# zb_pt4115_v1_1.net
KiCad netlist of a schematic drawn in EAGLE
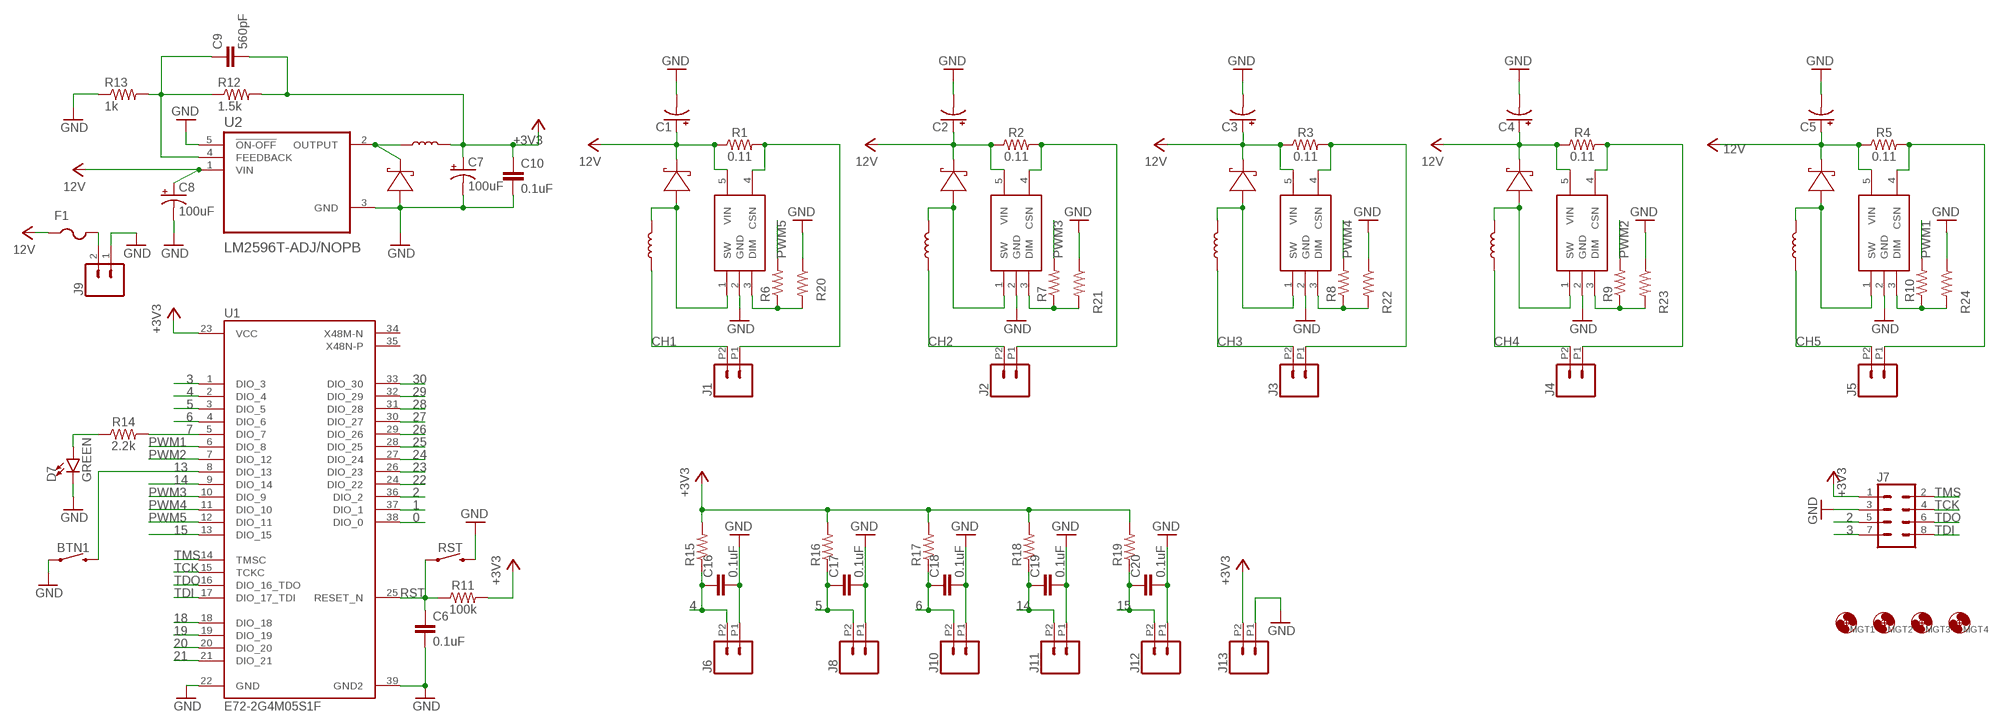
[diagram p0: schematic, sheet 1]

(export (version "E")
  (design (tool "Eeschema 10.0.6"))
  (components
    (comp (ref "BTN1")
      (value "MOMENTARY-SWITCH-SPST-SMD-4.6X2.8MM")
      (footprint "eagle-import:TACTILE_SWITCH_SMD_4.6X2.8MM")
      (libsource (lib "eagle-import") (part "MOMENTARY-SWITCH-SPST-SMD-4.6X2.8MM"))
    )
    (comp (ref "C1")
      (value "100uF")
      (footprint "eagle-import:EIA7343")
      (libsource (lib "eagle-import") (part "100UF-POLAR-EIA7343-16V-10%(TANT)"))
    )
    (comp (ref "C2")
      (value "100uF")
      (footprint "eagle-import:EIA7343")
      (libsource (lib "eagle-import") (part "100UF-POLAR-EIA7343-16V-10%(TANT)"))
    )
    (comp (ref "C3")
      (value "100uF")
      (footprint "eagle-import:EIA7343")
      (libsource (lib "eagle-import") (part "100UF-POLAR-EIA7343-16V-10%(TANT)"))
    )
    (comp (ref "C4")
      (value "100uF")
      (footprint "eagle-import:EIA7343")
      (libsource (lib "eagle-import") (part "100UF-POLAR-EIA7343-16V-10%(TANT)"))
    )
    (comp (ref "C5")
      (value "100uF")
      (footprint "eagle-import:EIA7343")
      (libsource (lib "eagle-import") (part "100UF-POLAR-EIA7343-16V-10%(TANT)"))
    )
    (comp (ref "C6")
      (value "0.1uF")
      (footprint "eagle-import:0603")
      (libsource (lib "eagle-import") (part "0.1UF-0603-100V-10%"))
    )
    (comp (ref "C7")
      (value "100uF")
      (footprint "eagle-import:PANASONIC_D")
      (libsource (lib "eagle-import") (part "SparkFun-Capacitors_510_100UF-POLAR-25V-20%(ELEC)"))
    )
    (comp (ref "C8")
      (value "100uF")
      (footprint "eagle-import:PANASONIC_D")
      (libsource (lib "eagle-import") (part "SparkFun-Capacitors_510_100UF-POLAR-25V-20%(ELEC)"))
    )
    (comp (ref "C9")
      (value "560pF")
      (footprint "eagle-import:0603")
      (libsource (lib "eagle-import") (part "560PF-0603-50V-5%"))
    )
    (comp (ref "C10")
      (value "0.1uF")
      (footprint "eagle-import:0603")
      (libsource (lib "eagle-import") (part "0.1UF-0603-25V-5%"))
    )
    (comp (ref "C16")
      (value "0.1uF")
      (footprint "eagle-import:0603")
      (libsource (lib "eagle-import") (part "0.1UF-0603-100V-10%"))
    )
    (comp (ref "C17")
      (value "0.1uF")
      (footprint "eagle-import:0603")
      (libsource (lib "eagle-import") (part "0.1UF-0603-100V-10%"))
    )
    (comp (ref "C18")
      (value "0.1uF")
      (footprint "eagle-import:0603")
      (libsource (lib "eagle-import") (part "0.1UF-0603-100V-10%"))
    )
    (comp (ref "C19")
      (value "0.1uF")
      (footprint "eagle-import:0603")
      (libsource (lib "eagle-import") (part "0.1UF-0603-100V-10%"))
    )
    (comp (ref "C20")
      (value "0.1uF")
      (footprint "eagle-import:0603")
      (libsource (lib "eagle-import") (part "0.1UF-0603-100V-10%"))
    )
    (comp (ref "D1")
      (value "SS18")
      (footprint "eagle-import:DIOM5227X270N")
      (fields (field (name "MOUSER_PART_NUMBER") "512-SS18"))
      (libsource (lib "eagle-import") (part "SS18"))
    )
    (comp (ref "D2")
      (value "SS18")
      (footprint "eagle-import:DIOM5227X270N")
      (fields (field (name "MOUSER_PART_NUMBER") "512-SS18"))
      (libsource (lib "eagle-import") (part "SS18"))
    )
    (comp (ref "D3")
      (value "SS18")
      (footprint "eagle-import:DIOM5227X270N")
      (fields (field (name "MOUSER_PART_NUMBER") "512-SS18"))
      (libsource (lib "eagle-import") (part "SS18"))
    )
    (comp (ref "D4")
      (value "SS18")
      (footprint "eagle-import:DIOM5227X270N")
      (fields (field (name "MOUSER_PART_NUMBER") "512-SS18"))
      (libsource (lib "eagle-import") (part "SS18"))
    )
    (comp (ref "D5")
      (value "SS18")
      (footprint "eagle-import:DIOM5227X270N")
      (fields (field (name "MOUSER_PART_NUMBER") "512-SS18"))
      (libsource (lib "eagle-import") (part "SS18"))
    )
    (comp (ref "D6")
      (value "SS18")
      (footprint "eagle-import:DIOM5227X270N")
      (fields (field (name "MOUSER_PART_NUMBER") "512-SS18"))
      (libsource (lib "eagle-import") (part "SS18"))
    )
    (comp (ref "D7")
      (value "GREEN")
      (footprint "eagle-import:LED-0603")
      (libsource (lib "eagle-import") (part "LED-GREEN0603"))
    )
    (comp (ref "F1")
      (value "PTCFUSE-1812")
      (footprint "eagle-import:1812")
      (libsource (lib "eagle-import") (part "PTCFUSE-1812"))
    )
    (comp (ref "IC1")
      (value "68uH")
      (footprint "eagle-import:INDPM102100X400N")
      (fields
        (field (name "MANUFACTURER_PART_NUMBER") "MSS1038-473MLB")
        (field (name "MOUSER_PART_NUMBER") "994-MSS1038-473MLB")
      )
      (libsource (lib "eagle-import") (part "MSS1038-473MLB"))
    )
    (comp (ref "IC2")
      (value "68uH")
      (footprint "eagle-import:INDPM102100X400N")
      (fields
        (field (name "MANUFACTURER_PART_NUMBER") "MSS1038-473MLB")
        (field (name "MOUSER_PART_NUMBER") "994-MSS1038-473MLB")
      )
      (libsource (lib "eagle-import") (part "MSS1038-473MLB"))
    )
    (comp (ref "IC3")
      (value "68uH")
      (footprint "eagle-import:INDPM102100X400N")
      (fields
        (field (name "MANUFACTURER_PART_NUMBER") "MSS1038-473MLB")
        (field (name "MOUSER_PART_NUMBER") "994-MSS1038-473MLB")
      )
      (libsource (lib "eagle-import") (part "MSS1038-473MLB"))
    )
    (comp (ref "IC4")
      (value "68uH")
      (footprint "eagle-import:INDPM102100X400N")
      (fields
        (field (name "MANUFACTURER_PART_NUMBER") "MSS1038-473MLB")
        (field (name "MOUSER_PART_NUMBER") "994-MSS1038-473MLB")
      )
      (libsource (lib "eagle-import") (part "MSS1038-473MLB"))
    )
    (comp (ref "IC5")
      (value "68uH")
      (footprint "eagle-import:INDPM102100X400N")
      (fields
        (field (name "MANUFACTURER_PART_NUMBER") "MSS1038-473MLB")
        (field (name "MOUSER_PART_NUMBER") "994-MSS1038-473MLB")
      )
      (libsource (lib "eagle-import") (part "MSS1038-473MLB"))
    )
    (comp (ref "IC6")
      (value "68uH")
      (footprint "eagle-import:INDPM102100X400N")
      (fields
        (field (name "MANUFACTURER_PART_NUMBER") "MSS1038-473MLB")
        (field (name "MOUSER_PART_NUMBER") "994-MSS1038-473MLB")
      )
      (libsource (lib "eagle-import") (part "MSS1038-473MLB"))
    )
    (comp (ref "J1")
      (value "CONN_022.54MM_SCREWTERM")
      (footprint "eagle-import:1X02_2.54_SCREWTERM")
      (libsource (lib "eagle-import") (part "CONN_022.54MM_SCREWTERM"))
    )
    (comp (ref "J2")
      (value "CONN_022.54MM_SCREWTERM")
      (footprint "eagle-import:1X02_2.54_SCREWTERM")
      (libsource (lib "eagle-import") (part "CONN_022.54MM_SCREWTERM"))
    )
    (comp (ref "J3")
      (value "CONN_022.54MM_SCREWTERM")
      (footprint "eagle-import:1X02_2.54_SCREWTERM")
      (libsource (lib "eagle-import") (part "CONN_022.54MM_SCREWTERM"))
    )
    (comp (ref "J4")
      (value "CONN_022.54MM_SCREWTERM")
      (footprint "eagle-import:1X02_2.54_SCREWTERM")
      (libsource (lib "eagle-import") (part "CONN_022.54MM_SCREWTERM"))
    )
    (comp (ref "J5")
      (value "CONN_022.54MM_SCREWTERM")
      (footprint "eagle-import:1X02_2.54_SCREWTERM")
      (libsource (lib "eagle-import") (part "CONN_022.54MM_SCREWTERM"))
    )
    (comp (ref "J6")
      (value "CONN_022.54MM_SCREWTERM")
      (footprint "eagle-import:1X02_2.54_SCREWTERM")
      (libsource (lib "eagle-import") (part "CONN_022.54MM_SCREWTERM"))
    )
    (comp (ref "J7")
      (value "CONN_04X2")
      (footprint "eagle-import:2X4")
      (libsource (lib "eagle-import") (part "CONN_04X2"))
    )
    (comp (ref "J8")
      (value "CONN_022.54MM_SCREWTERM")
      (footprint "eagle-import:1X02_2.54_SCREWTERM")
      (libsource (lib "eagle-import") (part "CONN_022.54MM_SCREWTERM"))
    )
    (comp (ref "J9")
      (value "CONN_025MM")
      (footprint "eagle-import:SCREWTERMINAL-5MM-2")
      (libsource (lib "eagle-import") (part "SparkFun-SEWPAD16_CONN_025MM"))
    )
    (comp (ref "J10")
      (value "CONN_022.54MM_SCREWTERM")
      (footprint "eagle-import:1X02_2.54_SCREWTERM")
      (libsource (lib "eagle-import") (part "CONN_022.54MM_SCREWTERM"))
    )
    (comp (ref "J11")
      (value "CONN_022.54MM_SCREWTERM")
      (footprint "eagle-import:1X02_2.54_SCREWTERM")
      (libsource (lib "eagle-import") (part "CONN_022.54MM_SCREWTERM"))
    )
    (comp (ref "J12")
      (value "CONN_022.54MM_SCREWTERM")
      (footprint "eagle-import:1X02_2.54_SCREWTERM")
      (libsource (lib "eagle-import") (part "CONN_022.54MM_SCREWTERM"))
    )
    (comp (ref "J13")
      (value "CONN_022.54MM_SCREWTERM")
      (footprint "eagle-import:1X02_2.54_SCREWTERM")
      (libsource (lib "eagle-import") (part "CONN_022.54MM_SCREWTERM"))
    )
    (comp (ref "MGT1")
      (value "MOUNT-HOLE3.0")
      (footprint "eagle-import:3,0")
      (libsource (lib "eagle-import") (part "MOUNT-HOLE3.0"))
    )
    (comp (ref "MGT2")
      (value "MOUNT-HOLE3.0")
      (footprint "eagle-import:3,0")
      (libsource (lib "eagle-import") (part "MOUNT-HOLE3.0"))
    )
    (comp (ref "MGT3")
      (value "MOUNT-HOLE3.0")
      (footprint "eagle-import:3,0")
      (libsource (lib "eagle-import") (part "MOUNT-HOLE3.0"))
    )
    (comp (ref "MGT4")
      (value "MOUNT-HOLE3.0")
      (footprint "eagle-import:3,0")
      (libsource (lib "eagle-import") (part "MOUNT-HOLE3.0"))
    )
    (comp (ref "R1")
      (value "0.11")
      (footprint "eagle-import:2010")
      (libsource (lib "eagle-import") (part "0.11OHM-2010-1/2W-1%"))
    )
    (comp (ref "R2")
      (value "0.11")
      (footprint "eagle-import:2010")
      (libsource (lib "eagle-import") (part "0.11OHM-2010-1/2W-1%"))
    )
    (comp (ref "R3")
      (value "0.11")
      (footprint "eagle-import:2010")
      (libsource (lib "eagle-import") (part "0.11OHM-2010-1/2W-1%"))
    )
    (comp (ref "R4")
      (value "0.11")
      (footprint "eagle-import:2010")
      (libsource (lib "eagle-import") (part "0.11OHM-2010-1/2W-1%"))
    )
    (comp (ref "R5")
      (value "0.11")
      (footprint "eagle-import:2010")
      (libsource (lib "eagle-import") (part "0.11OHM-2010-1/2W-1%"))
    )
    (comp (ref "R6")
      (value "100Ohm")
      (footprint "eagle-import:R0805")
      (libsource (lib "eagle-import") (part "R-US_R0805"))
    )
    (comp (ref "R7")
      (value "100Ohm")
      (footprint "eagle-import:R0805")
      (libsource (lib "eagle-import") (part "R-US_R0805"))
    )
    (comp (ref "R8")
      (value "100Ohm")
      (footprint "eagle-import:R0805")
      (libsource (lib "eagle-import") (part "R-US_R0805"))
    )
    (comp (ref "R9")
      (value "100Ohm")
      (footprint "eagle-import:R0805")
      (libsource (lib "eagle-import") (part "R-US_R0805"))
    )
    (comp (ref "R10")
      (value "100Ohm")
      (footprint "eagle-import:R0805")
      (libsource (lib "eagle-import") (part "R-US_R0805"))
    )
    (comp (ref "R11")
      (value "100k")
      (footprint "eagle-import:0603")
      (libsource (lib "eagle-import") (part "100KOHM-0603-1/10W-1%"))
    )
    (comp (ref "R12")
      (value "1.5k")
      (footprint "eagle-import:R0805")
      (libsource (lib "eagle-import") (part "R-US_R0805"))
    )
    (comp (ref "R13")
      (value "1k")
      (footprint "eagle-import:R0805")
      (libsource (lib "eagle-import") (part "R-US_R0805"))
    )
    (comp (ref "R14")
      (value "2.2k")
      (footprint "eagle-import:0603")
      (libsource (lib "eagle-import") (part "2.2KOHM-0603-1/10W-1%"))
    )
    (comp (ref "R15")
      (value "10k")
      (footprint "eagle-import:R0805")
      (libsource (lib "eagle-import") (part "R-US_R0805"))
    )
    (comp (ref "R16")
      (value "10k")
      (footprint "eagle-import:R0805")
      (libsource (lib "eagle-import") (part "R-US_R0805"))
    )
    (comp (ref "R17")
      (value "10k")
      (footprint "eagle-import:R0805")
      (libsource (lib "eagle-import") (part "R-US_R0805"))
    )
    (comp (ref "R18")
      (value "10k")
      (footprint "eagle-import:R0805")
      (libsource (lib "eagle-import") (part "R-US_R0805"))
    )
    (comp (ref "R19")
      (value "10k")
      (footprint "eagle-import:R0805")
      (libsource (lib "eagle-import") (part "R-US_R0805"))
    )
    (comp (ref "R20")
      (value "3k")
      (footprint "eagle-import:R0805")
      (libsource (lib "eagle-import") (part "R-US_R0805"))
    )
    (comp (ref "R21")
      (value "3k")
      (footprint "eagle-import:R0805")
      (libsource (lib "eagle-import") (part "R-US_R0805"))
    )
    (comp (ref "R22")
      (value "3k")
      (footprint "eagle-import:R0805")
      (libsource (lib "eagle-import") (part "R-US_R0805"))
    )
    (comp (ref "R23")
      (value "3k")
      (footprint "eagle-import:R0805")
      (libsource (lib "eagle-import") (part "R-US_R0805"))
    )
    (comp (ref "R24")
      (value "3k")
      (footprint "eagle-import:R0805")
      (libsource (lib "eagle-import") (part "R-US_R0805"))
    )
    (comp (ref "RST")
      (value "MOMENTARY-SWITCH-SPST-SMD-4.6X2.8MM")
      (footprint "eagle-import:TACTILE_SWITCH_SMD_4.6X2.8MM")
      (libsource (lib "eagle-import") (part "MOMENTARY-SWITCH-SPST-SMD-4.6X2.8MM"))
    )
    (comp (ref "U$1")
      (value "PT4115")
      (footprint "eagle-import:SOT-89-5")
      (fields (field (name "MF") "Pulse"))
      (libsource (lib "eagle-import") (part "PT4115"))
    )
    (comp (ref "U$2")
      (value "PT4115")
      (footprint "eagle-import:SOT-89-5")
      (fields (field (name "MF") "Pulse"))
      (libsource (lib "eagle-import") (part "PT4115"))
    )
    (comp (ref "U$3")
      (value "PT4115")
      (footprint "eagle-import:SOT-89-5")
      (fields (field (name "MF") "Pulse"))
      (libsource (lib "eagle-import") (part "PT4115"))
    )
    (comp (ref "U$4")
      (value "PT4115")
      (footprint "eagle-import:SOT-89-5")
      (fields (field (name "MF") "Pulse"))
      (libsource (lib "eagle-import") (part "PT4115"))
    )
    (comp (ref "U$5")
      (value "PT4115")
      (footprint "eagle-import:SOT-89-5")
      (fields (field (name "MF") "Pulse"))
      (libsource (lib "eagle-import") (part "PT4115"))
    )
    (comp (ref "U1")
      (value "E72-2G4M05S1F")
      (footprint "eagle-import:E72-2G4M05S1F")
      (libsource (lib "eagle-import") (part "E72-2G4M05S1F"))
    )
    (comp (ref "U2")
      (value "LM2596T-ADJ/NOPB")
      (footprint "eagle-import:TO170P1016X470X2092-5")
      (fields (field (name "MF") "Texas Instruments"))
      (libsource (lib "eagle-import") (part "LM2596T-ADJ/NOPB"))
    )
  )
  (nets
    (net (code "1") (name "+3V3") (class "Default")
      (node (ref "C10") (pin "1") (pinfunction "1_1") (pintype "passive"))
      (node (ref "C7") (pin "+") (pinfunction "+_+") (pintype "passive"))
      (node (ref "C9") (pin "2") (pinfunction "2_2") (pintype "passive"))
      (node (ref "IC6") (pin "2") (pinfunction "2_2") (pintype "bidirectional"))
      (node (ref "J13") (pin "P2") (pinfunction "2_P2") (pintype "passive"))
      (node (ref "J7") (pin "1") (pinfunction "1_1") (pintype "passive"))
      (node (ref "R11") (pin "2") (pinfunction "2_2") (pintype "passive"))
      (node (ref "R12") (pin "2") (pinfunction "2_2") (pintype "passive"))
      (node (ref "R15") (pin "2") (pinfunction "2_2") (pintype "passive"))
      (node (ref "R16") (pin "2") (pinfunction "2_2") (pintype "passive"))
      (node (ref "R17") (pin "2") (pinfunction "2_2") (pintype "passive"))
      (node (ref "R18") (pin "2") (pinfunction "2_2") (pintype "passive"))
      (node (ref "R19") (pin "2") (pinfunction "2_2") (pintype "passive"))
      (node (ref "U1") (pin "23") (pinfunction "VCC_23") (pintype "bidirectional"))
    )
    (net (code "2") (name "/0") (class "Default")
      (node (ref "U1") (pin "38") (pinfunction "DIO_0_38") (pintype "bidirectional"))
    )
    (net (code "3") (name "/1") (class "Default")
      (node (ref "U1") (pin "37") (pinfunction "DIO_1_37") (pintype "bidirectional"))
    )
    (net (code "4") (name "/2") (class "Default")
      (node (ref "J7") (pin "5") (pinfunction "5_5") (pintype "passive"))
      (node (ref "U1") (pin "36") (pinfunction "DIO_2_36") (pintype "bidirectional"))
    )
    (net (code "5") (name "/3") (class "Default")
      (node (ref "J7") (pin "7") (pinfunction "7_7") (pintype "passive"))
      (node (ref "U1") (pin "1") (pinfunction "DIO_3_1") (pintype "bidirectional"))
    )
    (net (code "6") (name "/4") (class "Default")
      (node (ref "C16") (pin "1") (pinfunction "1_1") (pintype "passive"))
      (node (ref "J6") (pin "P2") (pinfunction "2_P2") (pintype "passive"))
      (node (ref "R15") (pin "1") (pinfunction "1_1") (pintype "passive"))
      (node (ref "U1") (pin "2") (pinfunction "DIO_4_2") (pintype "bidirectional"))
    )
    (net (code "7") (name "/5") (class "Default")
      (node (ref "C17") (pin "1") (pinfunction "1_1") (pintype "passive"))
      (node (ref "J8") (pin "P2") (pinfunction "2_P2") (pintype "passive"))
      (node (ref "R16") (pin "1") (pinfunction "1_1") (pintype "passive"))
      (node (ref "U1") (pin "3") (pinfunction "DIO_5_3") (pintype "bidirectional"))
    )
    (net (code "8") (name "/6") (class "Default")
      (node (ref "C18") (pin "1") (pinfunction "1_1") (pintype "passive"))
      (node (ref "J10") (pin "P2") (pinfunction "2_P2") (pintype "passive"))
      (node (ref "R17") (pin "1") (pinfunction "1_1") (pintype "passive"))
      (node (ref "U1") (pin "4") (pinfunction "DIO_6_4") (pintype "bidirectional"))
    )
    (net (code "9") (name "/7") (class "Default")
      (node (ref "R14") (pin "2") (pinfunction "2_2") (pintype "passive"))
      (node (ref "U1") (pin "5") (pinfunction "DIO_7_5") (pintype "bidirectional"))
    )
    (net (code "10") (name "/13") (class "Default")
      (node (ref "BTN1") (pin "3") (pinfunction "2_3") (pintype "passive"))
      (node (ref "BTN1") (pin "4") (pinfunction "2_4") (pintype "passive"))
      (node (ref "U1") (pin "8") (pinfunction "DIO_13_8") (pintype "bidirectional"))
    )
    (net (code "11") (name "/14") (class "Default")
      (node (ref "C19") (pin "1") (pinfunction "1_1") (pintype "passive"))
      (node (ref "J11") (pin "P2") (pinfunction "2_P2") (pintype "passive"))
      (node (ref "R18") (pin "1") (pinfunction "1_1") (pintype "passive"))
      (node (ref "U1") (pin "9") (pinfunction "DIO_14_9") (pintype "bidirectional"))
    )
    (net (code "12") (name "/15") (class "Default")
      (node (ref "C20") (pin "1") (pinfunction "1_1") (pintype "passive"))
      (node (ref "J12") (pin "P2") (pinfunction "2_P2") (pintype "passive"))
      (node (ref "R19") (pin "1") (pinfunction "1_1") (pintype "passive"))
      (node (ref "U1") (pin "13") (pinfunction "DIO_15_13") (pintype "bidirectional"))
    )
    (net (code "13") (name "/18") (class "Default")
      (node (ref "U1") (pin "18") (pinfunction "DIO_18_18") (pintype "bidirectional"))
    )
    (net (code "14") (name "/19") (class "Default")
      (node (ref "U1") (pin "19") (pinfunction "DIO_19_19") (pintype "bidirectional"))
    )
    (net (code "15") (name "/20") (class "Default")
      (node (ref "U1") (pin "20") (pinfunction "DIO_20_20") (pintype "bidirectional"))
    )
    (net (code "16") (name "/21") (class "Default")
      (node (ref "U1") (pin "21") (pinfunction "DIO_21_21") (pintype "bidirectional"))
    )
    (net (code "17") (name "/22") (class "Default")
      (node (ref "U1") (pin "24") (pinfunction "DIO_22_24") (pintype "bidirectional"))
    )
    (net (code "18") (name "/23") (class "Default")
      (node (ref "U1") (pin "26") (pinfunction "DIO_23_26") (pintype "bidirectional"))
    )
    (net (code "19") (name "/24") (class "Default")
      (node (ref "U1") (pin "27") (pinfunction "DIO_24_27") (pintype "bidirectional"))
    )
    (net (code "20") (name "/25") (class "Default")
      (node (ref "U1") (pin "28") (pinfunction "DIO_25_28") (pintype "bidirectional"))
    )
    (net (code "21") (name "/26") (class "Default")
      (node (ref "U1") (pin "29") (pinfunction "DIO_26_29") (pintype "bidirectional"))
    )
    (net (code "22") (name "/27") (class "Default")
      (node (ref "U1") (pin "30") (pinfunction "DIO_27_30") (pintype "bidirectional"))
    )
    (net (code "23") (name "/28") (class "Default")
      (node (ref "U1") (pin "31") (pinfunction "DIO_28_31") (pintype "bidirectional"))
    )
    (net (code "24") (name "/29") (class "Default")
      (node (ref "U1") (pin "32") (pinfunction "DIO_29_32") (pintype "bidirectional"))
    )
    (net (code "25") (name "/30") (class "Default")
      (node (ref "U1") (pin "33") (pinfunction "DIO_30_33") (pintype "bidirectional"))
    )
    (net (code "26") (name "/CH1") (class "Default")
      (node (ref "IC1") (pin "1") (pinfunction "1_1") (pintype "bidirectional"))
      (node (ref "J1") (pin "P2") (pinfunction "2_P2") (pintype "passive"))
    )
    (net (code "27") (name "/CH2") (class "Default")
      (node (ref "IC2") (pin "1") (pinfunction "1_1") (pintype "bidirectional"))
      (node (ref "J2") (pin "P2") (pinfunction "2_P2") (pintype "passive"))
    )
    (net (code "28") (name "/CH3") (class "Default")
      (node (ref "IC3") (pin "1") (pinfunction "1_1") (pintype "bidirectional"))
      (node (ref "J3") (pin "P2") (pinfunction "2_P2") (pintype "passive"))
    )
    (net (code "29") (name "/CH4") (class "Default")
      (node (ref "IC4") (pin "1") (pinfunction "1_1") (pintype "bidirectional"))
      (node (ref "J4") (pin "P2") (pinfunction "2_P2") (pintype "passive"))
    )
    (net (code "30") (name "/CH5") (class "Default")
      (node (ref "IC5") (pin "1") (pinfunction "1_1") (pintype "bidirectional"))
      (node (ref "J5") (pin "P2") (pinfunction "2_P2") (pintype "passive"))
    )
    (net (code "31") (name "/PWM1") (class "Default")
      (node (ref "R10") (pin "2") (pinfunction "2_2") (pintype "passive"))
      (node (ref "U1") (pin "6") (pinfunction "DIO_8_6") (pintype "bidirectional"))
    )
    (net (code "32") (name "/PWM2") (class "Default")
      (node (ref "R9") (pin "2") (pinfunction "2_2") (pintype "passive"))
      (node (ref "U1") (pin "7") (pinfunction "DIO_12_7") (pintype "bidirectional"))
    )
    (net (code "33") (name "/PWM3") (class "Default")
      (node (ref "R7") (pin "2") (pinfunction "2_2") (pintype "passive"))
      (node (ref "U1") (pin "10") (pinfunction "DIO_9_10") (pintype "bidirectional"))
    )
    (net (code "34") (name "/PWM4") (class "Default")
      (node (ref "R8") (pin "2") (pinfunction "2_2") (pintype "passive"))
      (node (ref "U1") (pin "11") (pinfunction "DIO_10_11") (pintype "bidirectional"))
    )
    (net (code "35") (name "/PWM5") (class "Default")
      (node (ref "R6") (pin "2") (pinfunction "2_2") (pintype "passive"))
      (node (ref "U1") (pin "12") (pinfunction "DIO_11_12") (pintype "bidirectional"))
    )
    (net (code "36") (name "/RST") (class "Default")
      (node (ref "C6") (pin "1") (pinfunction "1_1") (pintype "passive"))
      (node (ref "R11") (pin "1") (pinfunction "1_1") (pintype "passive"))
      (node (ref "RST") (pin "1") (pinfunction "1_1") (pintype "passive"))
      (node (ref "RST") (pin "2") (pinfunction "1_2") (pintype "passive"))
      (node (ref "U1") (pin "25") (pinfunction "RESET_N_25") (pintype "bidirectional"))
    )
    (net (code "37") (name "/TCK") (class "Default")
      (node (ref "J7") (pin "4") (pinfunction "4_4") (pintype "passive"))
      (node (ref "U1") (pin "15") (pinfunction "TCKC_15") (pintype "bidirectional"))
    )
    (net (code "38") (name "/TDI") (class "Default")
      (node (ref "J7") (pin "8") (pinfunction "8_8") (pintype "passive"))
      (node (ref "U1") (pin "17") (pinfunction "DIO_17_TDI_17") (pintype "bidirectional"))
    )
    (net (code "39") (name "/TDO") (class "Default")
      (node (ref "J7") (pin "6") (pinfunction "6_6") (pintype "passive"))
      (node (ref "U1") (pin "16") (pinfunction "DIO_16_TDO_16") (pintype "bidirectional"))
    )
    (net (code "40") (name "/TMS") (class "Default")
      (node (ref "J7") (pin "2") (pinfunction "2_2") (pintype "passive"))
      (node (ref "U1") (pin "14") (pinfunction "TMSC_14") (pintype "bidirectional"))
    )
    (net (code "41") (name "12V") (class "Default")
      (node (ref "C1") (pin "A") (pinfunction "+_A") (pintype "passive"))
      (node (ref "C2") (pin "A") (pinfunction "+_A") (pintype "passive"))
      (node (ref "C3") (pin "A") (pinfunction "+_A") (pintype "passive"))
      (node (ref "C4") (pin "A") (pinfunction "+_A") (pintype "passive"))
      (node (ref "C5") (pin "A") (pinfunction "+_A") (pintype "passive"))
      (node (ref "C8") (pin "+") (pinfunction "+_+") (pintype "passive"))
      (node (ref "D1") (pin "1") (pinfunction "K_1") (pintype "bidirectional"))
      (node (ref "D2") (pin "1") (pinfunction "K_1") (pintype "bidirectional"))
      (node (ref "D3") (pin "1") (pinfunction "K_1") (pintype "bidirectional"))
      (node (ref "D4") (pin "1") (pinfunction "K_1") (pintype "bidirectional"))
      (node (ref "D5") (pin "1") (pinfunction "K_1") (pintype "bidirectional"))
      (node (ref "F1") (pin "1") (pinfunction "1_1") (pintype "passive"))
      (node (ref "F1") (pin "2") (pinfunction "2_2") (pintype "passive"))
      (node (ref "J9") (pin "2") (pinfunction "2_2") (pintype "passive"))
      (node (ref "R1") (pin "1") (pinfunction "1_1") (pintype "passive"))
      (node (ref "R2") (pin "1") (pinfunction "1_1") (pintype "passive"))
      (node (ref "R3") (pin "1") (pinfunction "1_1") (pintype "passive"))
      (node (ref "R4") (pin "1") (pinfunction "1_1") (pintype "passive"))
      (node (ref "R5") (pin "1") (pinfunction "1_1") (pintype "passive"))
      (node (ref "U$1") (pin "5") (pinfunction "VIN_5") (pintype "bidirectional"))
      (node (ref "U$2") (pin "5") (pinfunction "VIN_5") (pintype "bidirectional"))
      (node (ref "U$3") (pin "5") (pinfunction "VIN_5") (pintype "bidirectional"))
      (node (ref "U$4") (pin "5") (pinfunction "VIN_5") (pintype "bidirectional"))
      (node (ref "U$5") (pin "5") (pinfunction "VIN_5") (pintype "bidirectional"))
      (node (ref "U2") (pin "1") (pinfunction "VIN_1") (pintype "input"))
    )
    (net (code "42") (name "GND") (class "Default")
      (node (ref "BTN1") (pin "1") (pinfunction "1_1") (pintype "passive"))
      (node (ref "BTN1") (pin "2") (pinfunction "1_2") (pintype "passive"))
      (node (ref "C1") (pin "C") (pinfunction "-_C") (pintype "passive"))
      (node (ref "C10") (pin "2") (pinfunction "2_2") (pintype "passive"))
      (node (ref "C16") (pin "2") (pinfunction "2_2") (pintype "passive"))
      (node (ref "C17") (pin "2") (pinfunction "2_2") (pintype "passive"))
      (node (ref "C18") (pin "2") (pinfunction "2_2") (pintype "passive"))
      (node (ref "C19") (pin "2") (pinfunction "2_2") (pintype "passive"))
      (node (ref "C2") (pin "C") (pinfunction "-_C") (pintype "passive"))
      (node (ref "C20") (pin "2") (pinfunction "2_2") (pintype "passive"))
      (node (ref "C3") (pin "C") (pinfunction "-_C") (pintype "passive"))
      (node (ref "C4") (pin "C") (pinfunction "-_C") (pintype "passive"))
      (node (ref "C5") (pin "C") (pinfunction "-_C") (pintype "passive"))
      (node (ref "C6") (pin "2") (pinfunction "2_2") (pintype "passive"))
      (node (ref "C7") (pin "-") (pinfunction "-_-") (pintype "passive"))
      (node (ref "C8") (pin "-") (pinfunction "-_-") (pintype "passive"))
      (node (ref "D6") (pin "2") (pinfunction "A_2") (pintype "bidirectional"))
      (node (ref "D7") (pin "C") (pinfunction "C_C") (pintype "passive"))
      (node (ref "J10") (pin "P1") (pinfunction "1_P1") (pintype "passive"))
      (node (ref "J11") (pin "P1") (pinfunction "1_P1") (pintype "passive"))
      (node (ref "J12") (pin "P1") (pinfunction "1_P1") (pintype "passive"))
      (node (ref "J13") (pin "P1") (pinfunction "1_P1") (pintype "passive"))
      (node (ref "J6") (pin "P1") (pinfunction "1_P1") (pintype "passive"))
      (node (ref "J7") (pin "3") (pinfunction "3_3") (pintype "passive"))
      (node (ref "J8") (pin "P1") (pinfunction "1_P1") (pintype "passive"))
      (node (ref "J9") (pin "1") (pinfunction "1_1") (pintype "passive"))
      (node (ref "R13") (pin "1") (pinfunction "1_1") (pintype "passive"))
      (node (ref "R20") (pin "1") (pinfunction "1_1") (pintype "passive"))
      (node (ref "R21") (pin "1") (pinfunction "1_1") (pintype "passive"))
      (node (ref "R22") (pin "1") (pinfunction "1_1") (pintype "passive"))
      (node (ref "R23") (pin "1") (pinfunction "1_1") (pintype "passive"))
      (node (ref "R24") (pin "1") (pinfunction "1_1") (pintype "passive"))
      (node (ref "RST") (pin "3") (pinfunction "2_3") (pintype "passive"))
      (node (ref "RST") (pin "4") (pinfunction "2_4") (pintype "passive"))
      (node (ref "U$1") (pin "2") (pinfunction "GND_2") (pintype "bidirectional"))
      (node (ref "U$2") (pin "2") (pinfunction "GND_2") (pintype "bidirectional"))
      (node (ref "U$3") (pin "2") (pinfunction "GND_2") (pintype "bidirectional"))
      (node (ref "U$4") (pin "2") (pinfunction "GND_2") (pintype "bidirectional"))
      (node (ref "U$5") (pin "2") (pinfunction "GND_2") (pintype "bidirectional"))
      (node (ref "U1") (pin "22") (pinfunction "GND_22") (pintype "bidirectional"))
      (node (ref "U1") (pin "39") (pinfunction "GND2_39") (pintype "bidirectional"))
      (node (ref "U2") (pin "3") (pinfunction "GND_3") (pintype "power_in"))
      (node (ref "U2") (pin "5") (pinfunction "~{ON-OFF}_5") (pintype "input"))
    )
    (net (code "43") (name "Net-(D1-A)") (class "Default")
      (node (ref "D1") (pin "2") (pinfunction "A_2") (pintype "bidirectional"))
      (node (ref "IC1") (pin "2") (pinfunction "2_2") (pintype "bidirectional"))
      (node (ref "U$1") (pin "1") (pinfunction "SW_1") (pintype "bidirectional"))
    )
    (net (code "44") (name "Net-(D2-A)") (class "Default")
      (node (ref "D2") (pin "2") (pinfunction "A_2") (pintype "bidirectional"))
      (node (ref "IC2") (pin "2") (pinfunction "2_2") (pintype "bidirectional"))
      (node (ref "U$2") (pin "1") (pinfunction "SW_1") (pintype "bidirectional"))
    )
    (net (code "45") (name "Net-(D3-A)") (class "Default")
      (node (ref "D3") (pin "2") (pinfunction "A_2") (pintype "bidirectional"))
      (node (ref "IC3") (pin "2") (pinfunction "2_2") (pintype "bidirectional"))
      (node (ref "U$3") (pin "1") (pinfunction "SW_1") (pintype "bidirectional"))
    )
    (net (code "46") (name "Net-(D4-A)") (class "Default")
      (node (ref "D4") (pin "2") (pinfunction "A_2") (pintype "bidirectional"))
      (node (ref "IC4") (pin "2") (pinfunction "2_2") (pintype "bidirectional"))
      (node (ref "U$4") (pin "1") (pinfunction "SW_1") (pintype "bidirectional"))
    )
    (net (code "47") (name "Net-(D5-A)") (class "Default")
      (node (ref "D5") (pin "2") (pinfunction "A_2") (pintype "bidirectional"))
      (node (ref "IC5") (pin "2") (pinfunction "2_2") (pintype "bidirectional"))
      (node (ref "U$5") (pin "1") (pinfunction "SW_1") (pintype "bidirectional"))
    )
    (net (code "48") (name "Net-(D6-K)") (class "Default")
      (node (ref "D6") (pin "1") (pinfunction "K_1") (pintype "bidirectional"))
      (node (ref "IC6") (pin "1") (pinfunction "1_1") (pintype "bidirectional"))
      (node (ref "U2") (pin "2") (pinfunction "OUTPUT_2") (pintype "output"))
    )
    (net (code "49") (name "Net-(D7-PadA)") (class "Default")
      (node (ref "D7") (pin "A") (pinfunction "A_A") (pintype "passive"))
      (node (ref "R14") (pin "1") (pinfunction "1_1") (pintype "passive"))
    )
    (net (code "50") (name "Net-(J1-1)") (class "Default")
      (node (ref "J1") (pin "P1") (pinfunction "1_P1") (pintype "passive"))
      (node (ref "R1") (pin "2") (pinfunction "2_2") (pintype "passive"))
      (node (ref "U$1") (pin "4") (pinfunction "CSN_4") (pintype "bidirectional"))
    )
    (net (code "51") (name "Net-(J2-1)") (class "Default")
      (node (ref "J2") (pin "P1") (pinfunction "1_P1") (pintype "passive"))
      (node (ref "R2") (pin "2") (pinfunction "2_2") (pintype "passive"))
      (node (ref "U$2") (pin "4") (pinfunction "CSN_4") (pintype "bidirectional"))
    )
    (net (code "52") (name "Net-(J3-1)") (class "Default")
      (node (ref "J3") (pin "P1") (pinfunction "1_P1") (pintype "passive"))
      (node (ref "R3") (pin "2") (pinfunction "2_2") (pintype "passive"))
      (node (ref "U$3") (pin "4") (pinfunction "CSN_4") (pintype "bidirectional"))
    )
    (net (code "53") (name "Net-(J4-1)") (class "Default")
      (node (ref "J4") (pin "P1") (pinfunction "1_P1") (pintype "passive"))
      (node (ref "R4") (pin "2") (pinfunction "2_2") (pintype "passive"))
      (node (ref "U$4") (pin "4") (pinfunction "CSN_4") (pintype "bidirectional"))
    )
    (net (code "54") (name "Net-(J5-1)") (class "Default")
      (node (ref "J5") (pin "P1") (pinfunction "1_P1") (pintype "passive"))
      (node (ref "R5") (pin "2") (pinfunction "2_2") (pintype "passive"))
      (node (ref "U$5") (pin "4") (pinfunction "CSN_4") (pintype "bidirectional"))
    )
    (net (code "55") (name "Net-(U$1-DIM)") (class "Default")
      (node (ref "R20") (pin "2") (pinfunction "2_2") (pintype "passive"))
      (node (ref "R6") (pin "1") (pinfunction "1_1") (pintype "passive"))
      (node (ref "U$1") (pin "3") (pinfunction "DIM_3") (pintype "bidirectional"))
    )
    (net (code "56") (name "Net-(U$2-DIM)") (class "Default")
      (node (ref "R21") (pin "2") (pinfunction "2_2") (pintype "passive"))
      (node (ref "R7") (pin "1") (pinfunction "1_1") (pintype "passive"))
      (node (ref "U$2") (pin "3") (pinfunction "DIM_3") (pintype "bidirectional"))
    )
    (net (code "57") (name "Net-(U$3-DIM)") (class "Default")
      (node (ref "R22") (pin "2") (pinfunction "2_2") (pintype "passive"))
      (node (ref "R8") (pin "1") (pinfunction "1_1") (pintype "passive"))
      (node (ref "U$3") (pin "3") (pinfunction "DIM_3") (pintype "bidirectional"))
    )
    (net (code "58") (name "Net-(U$4-DIM)") (class "Default")
      (node (ref "R23") (pin "2") (pinfunction "2_2") (pintype "passive"))
      (node (ref "R9") (pin "1") (pinfunction "1_1") (pintype "passive"))
      (node (ref "U$4") (pin "3") (pinfunction "DIM_3") (pintype "bidirectional"))
    )
    (net (code "59") (name "Net-(U$5-DIM)") (class "Default")
      (node (ref "R10") (pin "1") (pinfunction "1_1") (pintype "passive"))
      (node (ref "R24") (pin "2") (pinfunction "2_2") (pintype "passive"))
      (node (ref "U$5") (pin "3") (pinfunction "DIM_3") (pintype "bidirectional"))
    )
    (net (code "60") (name "Net-(U2-FEEDBACK)") (class "Default")
      (node (ref "C9") (pin "1") (pinfunction "1_1") (pintype "passive"))
      (node (ref "R12") (pin "1") (pinfunction "1_1") (pintype "passive"))
      (node (ref "R13") (pin "2") (pinfunction "2_2") (pintype "passive"))
      (node (ref "U2") (pin "4") (pinfunction "FEEDBACK_4") (pintype "input"))
    )
    (net (code "61") (name "unconnected-(U1-X48M-N-Pad34)") (class "Default")
      (node (ref "U1") (pin "34") (pinfunction "X48M-N_34") (pintype "bidirectional"))
    )
    (net (code "62") (name "unconnected-(U1-X48N-P-Pad35)") (class "Default")
      (node (ref "U1") (pin "35") (pinfunction "X48N-P_35") (pintype "bidirectional"))
    )
  )
)
